# adc.net
KiCad netlist of a schematic drawn in EAGLE
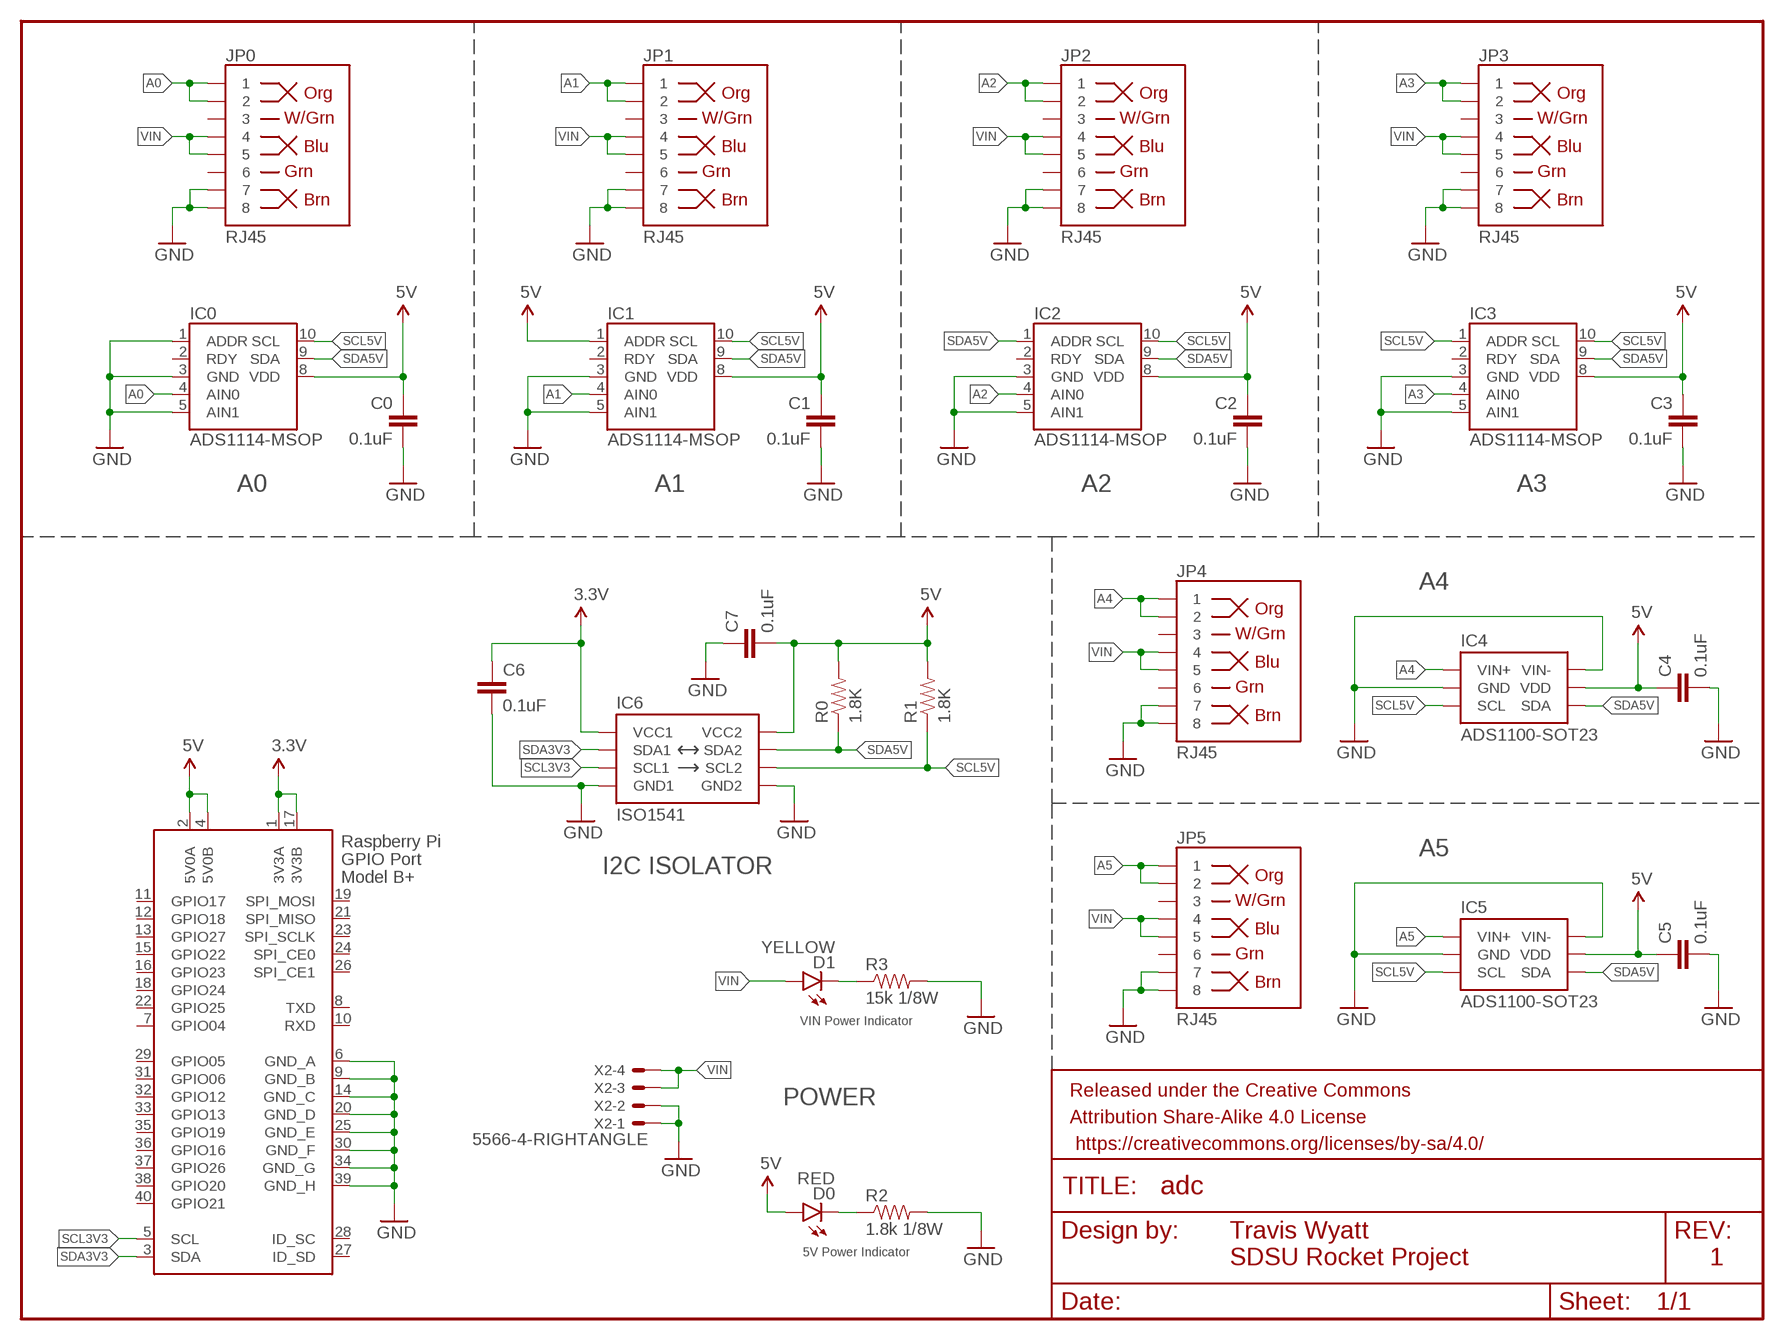
[diagram p0: schematic, sheet 1]

(export (version "E")
  (design (tool "Eeschema 10.0.6"))
  (components
    (comp (ref "C0")
      (value "0.1uF")
      (footprint "eagle-import:0603-CAP")
      (libsource (lib "eagle-import") (part "CAP0603-CAP"))
    )
    (comp (ref "C1")
      (value "0.1uF")
      (footprint "eagle-import:0603-CAP")
      (libsource (lib "eagle-import") (part "CAP0603-CAP"))
    )
    (comp (ref "C2")
      (value "0.1uF")
      (footprint "eagle-import:0603-CAP")
      (libsource (lib "eagle-import") (part "CAP0603-CAP"))
    )
    (comp (ref "C3")
      (value "0.1uF")
      (footprint "eagle-import:0603-CAP")
      (libsource (lib "eagle-import") (part "CAP0603-CAP"))
    )
    (comp (ref "C4")
      (value "0.1uF")
      (footprint "eagle-import:0603-CAP")
      (libsource (lib "eagle-import") (part "CAP0603-CAP"))
    )
    (comp (ref "C5")
      (value "0.1uF")
      (footprint "eagle-import:0603-CAP")
      (libsource (lib "eagle-import") (part "CAP0603-CAP"))
    )
    (comp (ref "C6")
      (value "0.1uF")
      (footprint "eagle-import:0603-CAP")
      (libsource (lib "eagle-import") (part "CAP0603-CAP"))
    )
    (comp (ref "C7")
      (value "0.1uF")
      (footprint "eagle-import:0603-CAP")
      (libsource (lib "eagle-import") (part "CAP0603-CAP"))
    )
    (comp (ref "D0")
      (value "RED")
      (footprint "eagle-import:LED-0603")
      (libsource (lib "eagle-import") (part "LED0603"))
    )
    (comp (ref "D1")
      (value "YELLOW")
      (footprint "eagle-import:LED-0603")
      (libsource (lib "eagle-import") (part "LED0603"))
    )
    (comp (ref "FRAME1")
      (value "FRAME-LETTER")
      (footprint "eagle-import:CREATIVE_COMMONS")
      (libsource (lib "eagle-import") (part "FRAME-LETTER"))
    )
    (comp (ref "IC0")
      (value "ADS1114-MSOP")
      (footprint "eagle-import:MSOP10")
      (libsource (lib "eagle-import") (part "ADS1114-MSOP"))
    )
    (comp (ref "IC1")
      (value "ADS1114-MSOP")
      (footprint "eagle-import:MSOP10")
      (libsource (lib "eagle-import") (part "ADS1114-MSOP"))
    )
    (comp (ref "IC2")
      (value "ADS1114-MSOP")
      (footprint "eagle-import:MSOP10")
      (libsource (lib "eagle-import") (part "ADS1114-MSOP"))
    )
    (comp (ref "IC3")
      (value "ADS1114-MSOP")
      (footprint "eagle-import:MSOP10")
      (libsource (lib "eagle-import") (part "ADS1114-MSOP"))
    )
    (comp (ref "IC4")
      (value "ADS1100-SOT23")
      (footprint "eagle-import:SOT23-6")
      (libsource (lib "eagle-import") (part "ADS1100-SOT23"))
    )
    (comp (ref "IC5")
      (value "ADS1100-SOT23")
      (footprint "eagle-import:SOT23-6")
      (libsource (lib "eagle-import") (part "ADS1100-SOT23"))
    )
    (comp (ref "IC6")
      (value "ISO1541")
      (footprint "eagle-import:SOIC8")
      (libsource (lib "eagle-import") (part "ISO1541-SOIC"))
    )
    (comp (ref "JP0")
      (value "RJ45")
      (footprint "eagle-import:RJ45-8")
      (libsource (lib "eagle-import") (part "RJ45-8PTH"))
    )
    (comp (ref "JP1")
      (value "RJ45")
      (footprint "eagle-import:RJ45-8")
      (libsource (lib "eagle-import") (part "RJ45-8PTH"))
    )
    (comp (ref "JP2")
      (value "RJ45")
      (footprint "eagle-import:RJ45-8")
      (libsource (lib "eagle-import") (part "RJ45-8PTH"))
    )
    (comp (ref "JP3")
      (value "RJ45")
      (footprint "eagle-import:RJ45-8")
      (libsource (lib "eagle-import") (part "RJ45-8PTH"))
    )
    (comp (ref "JP4")
      (value "RJ45")
      (footprint "eagle-import:RJ45-8")
      (libsource (lib "eagle-import") (part "RJ45-8PTH"))
    )
    (comp (ref "JP5")
      (value "RJ45")
      (footprint "eagle-import:RJ45-8")
      (libsource (lib "eagle-import") (part "RJ45-8PTH"))
    )
    (comp (ref "R0")
      (value "1.8K")
      (footprint "eagle-import:0603-RES")
      (libsource (lib "eagle-import") (part "RESISTOR0603-RES"))
    )
    (comp (ref "R1")
      (value "1.8K")
      (footprint "eagle-import:0603-RES")
      (libsource (lib "eagle-import") (part "RESISTOR0603-RES"))
    )
    (comp (ref "R2")
      (value "1.8k 1/8W")
      (footprint "eagle-import:0603-RES")
      (libsource (lib "eagle-import") (part "SparkFun-Resistors_RESISTOR0603-RES"))
    )
    (comp (ref "R3")
      (value "15k 1/8W")
      (footprint "eagle-import:0603-RES")
      (libsource (lib "eagle-import") (part "SparkFun-Resistors_RESISTOR0603-RES"))
    )
    (comp (ref "X1")
      (value "RASPI_BOARD_B+#_H")
      (footprint "eagle-import:RASPI_BOARD_B+HAT")
      (libsource (lib "eagle-import") (part "RASPI_BOARD_B+#_H"))
    )
    (comp (ref "X2")
      (value "5566-4-RIGHTANGLE")
      (footprint "eagle-import:5566-4")
      (libsource (lib "eagle-import") (part "5566-4-RIGHTANGLE"))
    )
  )
  (nets
    (net (code "1") (name "3.3V") (class "Default")
      (node (ref "C6") (pin "1") (pinfunction "1_1") (pintype "passive"))
      (node (ref "IC6") (pin "1") (pinfunction "VCC1_1") (pintype "power_in"))
      (node (ref "X1") (pin "1") (pinfunction "3V3A_1") (pintype "power_in"))
      (node (ref "X1") (pin "17") (pinfunction "3V3B_17") (pintype "power_in"))
    )
    (net (code "2") (name "5V") (class "Default")
      (node (ref "C0") (pin "1") (pinfunction "1_1") (pintype "passive"))
      (node (ref "C1") (pin "1") (pinfunction "1_1") (pintype "passive"))
      (node (ref "C2") (pin "1") (pinfunction "1_1") (pintype "passive"))
      (node (ref "C3") (pin "1") (pinfunction "1_1") (pintype "passive"))
      (node (ref "C4") (pin "1") (pinfunction "1_1") (pintype "passive"))
      (node (ref "C5") (pin "1") (pinfunction "1_1") (pintype "passive"))
      (node (ref "C7") (pin "2") (pinfunction "2_2") (pintype "passive"))
      (node (ref "D0") (pin "A") (pinfunction "A_A") (pintype "passive"))
      (node (ref "IC0") (pin "8") (pinfunction "VDD_8") (pintype "power_in"))
      (node (ref "IC1") (pin "1") (pinfunction "ADDR_1") (pintype "bidirectional"))
      (node (ref "IC1") (pin "8") (pinfunction "VDD_8") (pintype "power_in"))
      (node (ref "IC2") (pin "8") (pinfunction "VDD_8") (pintype "power_in"))
      (node (ref "IC3") (pin "8") (pinfunction "VDD_8") (pintype "power_in"))
      (node (ref "IC4") (pin "5") (pinfunction "VDD_5") (pintype "power_in"))
      (node (ref "IC5") (pin "5") (pinfunction "VDD_5") (pintype "power_in"))
      (node (ref "IC6") (pin "8") (pinfunction "VCC2_8") (pintype "power_in"))
      (node (ref "R0") (pin "2") (pinfunction "2_2") (pintype "passive"))
      (node (ref "R1") (pin "2") (pinfunction "2_2") (pintype "passive"))
      (node (ref "X1") (pin "2") (pinfunction "5V0A_2") (pintype "power_in"))
      (node (ref "X1") (pin "4") (pinfunction "5V0B_4") (pintype "power_in"))
    )
    (net (code "3") (name "A0") (class "Default")
      (node (ref "IC0") (pin "4") (pinfunction "AIN0_4") (pintype "input"))
      (node (ref "JP0") (pin "1") (pinfunction "1_1") (pintype "bidirectional"))
      (node (ref "JP0") (pin "2") (pinfunction "2_2") (pintype "bidirectional"))
    )
    (net (code "4") (name "A1") (class "Default")
      (node (ref "IC1") (pin "4") (pinfunction "AIN0_4") (pintype "input"))
      (node (ref "JP1") (pin "1") (pinfunction "1_1") (pintype "bidirectional"))
      (node (ref "JP1") (pin "2") (pinfunction "2_2") (pintype "bidirectional"))
    )
    (net (code "5") (name "A2") (class "Default")
      (node (ref "IC2") (pin "4") (pinfunction "AIN0_4") (pintype "input"))
      (node (ref "JP2") (pin "1") (pinfunction "1_1") (pintype "bidirectional"))
      (node (ref "JP2") (pin "2") (pinfunction "2_2") (pintype "bidirectional"))
    )
    (net (code "6") (name "A3") (class "Default")
      (node (ref "IC3") (pin "4") (pinfunction "AIN0_4") (pintype "input"))
      (node (ref "JP3") (pin "1") (pinfunction "1_1") (pintype "bidirectional"))
      (node (ref "JP3") (pin "2") (pinfunction "2_2") (pintype "bidirectional"))
    )
    (net (code "7") (name "A4") (class "Default")
      (node (ref "IC4") (pin "1") (pinfunction "VIN+_1") (pintype "input"))
      (node (ref "JP4") (pin "1") (pinfunction "1_1") (pintype "bidirectional"))
      (node (ref "JP4") (pin "2") (pinfunction "2_2") (pintype "bidirectional"))
    )
    (net (code "8") (name "A5") (class "Default")
      (node (ref "IC5") (pin "1") (pinfunction "VIN+_1") (pintype "input"))
      (node (ref "JP5") (pin "1") (pinfunction "1_1") (pintype "bidirectional"))
      (node (ref "JP5") (pin "2") (pinfunction "2_2") (pintype "bidirectional"))
    )
    (net (code "9") (name "GND") (class "Default")
      (node (ref "C0") (pin "2") (pinfunction "2_2") (pintype "passive"))
      (node (ref "C1") (pin "2") (pinfunction "2_2") (pintype "passive"))
      (node (ref "C2") (pin "2") (pinfunction "2_2") (pintype "passive"))
      (node (ref "C3") (pin "2") (pinfunction "2_2") (pintype "passive"))
      (node (ref "C4") (pin "2") (pinfunction "2_2") (pintype "passive"))
      (node (ref "C5") (pin "2") (pinfunction "2_2") (pintype "passive"))
      (node (ref "C6") (pin "2") (pinfunction "2_2") (pintype "passive"))
      (node (ref "C7") (pin "1") (pinfunction "1_1") (pintype "passive"))
      (node (ref "IC0") (pin "1") (pinfunction "ADDR_1") (pintype "bidirectional"))
      (node (ref "IC0") (pin "3") (pinfunction "GND_3") (pintype "power_in"))
      (node (ref "IC0") (pin "5") (pinfunction "AIN1_5") (pintype "input"))
      (node (ref "IC1") (pin "3") (pinfunction "GND_3") (pintype "power_in"))
      (node (ref "IC1") (pin "5") (pinfunction "AIN1_5") (pintype "input"))
      (node (ref "IC2") (pin "3") (pinfunction "GND_3") (pintype "power_in"))
      (node (ref "IC2") (pin "5") (pinfunction "AIN1_5") (pintype "input"))
      (node (ref "IC3") (pin "3") (pinfunction "GND_3") (pintype "power_in"))
      (node (ref "IC3") (pin "5") (pinfunction "AIN1_5") (pintype "input"))
      (node (ref "IC4") (pin "2") (pinfunction "GND_2") (pintype "power_in"))
      (node (ref "IC4") (pin "6") (pinfunction "VIN-_6") (pintype "input"))
      (node (ref "IC5") (pin "2") (pinfunction "GND_2") (pintype "power_in"))
      (node (ref "IC5") (pin "6") (pinfunction "VIN-_6") (pintype "input"))
      (node (ref "IC6") (pin "4") (pinfunction "GND1_4") (pintype "power_in"))
      (node (ref "IC6") (pin "5") (pinfunction "GND2_5") (pintype "power_in"))
      (node (ref "JP0") (pin "7") (pinfunction "7_7") (pintype "bidirectional"))
      (node (ref "JP0") (pin "8") (pinfunction "8_8") (pintype "bidirectional"))
      (node (ref "JP1") (pin "7") (pinfunction "7_7") (pintype "bidirectional"))
      (node (ref "JP1") (pin "8") (pinfunction "8_8") (pintype "bidirectional"))
      (node (ref "JP2") (pin "7") (pinfunction "7_7") (pintype "bidirectional"))
      (node (ref "JP2") (pin "8") (pinfunction "8_8") (pintype "bidirectional"))
      (node (ref "JP3") (pin "7") (pinfunction "7_7") (pintype "bidirectional"))
      (node (ref "JP3") (pin "8") (pinfunction "8_8") (pintype "bidirectional"))
      (node (ref "JP4") (pin "7") (pinfunction "7_7") (pintype "bidirectional"))
      (node (ref "JP4") (pin "8") (pinfunction "8_8") (pintype "bidirectional"))
      (node (ref "JP5") (pin "7") (pinfunction "7_7") (pintype "bidirectional"))
      (node (ref "JP5") (pin "8") (pinfunction "8_8") (pintype "bidirectional"))
      (node (ref "R2") (pin "2") (pinfunction "2_2") (pintype "passive"))
      (node (ref "R3") (pin "2") (pinfunction "2_2") (pintype "passive"))
      (node (ref "X1") (pin "14") (pinfunction "GND_C_14") (pintype "power_in"))
      (node (ref "X1") (pin "20") (pinfunction "GND_D_20") (pintype "power_in"))
      (node (ref "X1") (pin "25") (pinfunction "GND_E_25") (pintype "power_in"))
      (node (ref "X1") (pin "30") (pinfunction "GND_F_30") (pintype "power_in"))
      (node (ref "X1") (pin "34") (pinfunction "GND_G_34") (pintype "power_in"))
      (node (ref "X1") (pin "39") (pinfunction "GND_H_39") (pintype "power_in"))
      (node (ref "X1") (pin "6") (pinfunction "GND_A_6") (pintype "power_in"))
      (node (ref "X1") (pin "9") (pinfunction "GND_B_9") (pintype "power_in"))
      (node (ref "X2") (pin "1") (pinfunction "S_1") (pintype "passive"))
      (node (ref "X2") (pin "2") (pinfunction "S_2") (pintype "passive"))
    )
    (net (code "10") (name "Net-(D0-PadC)") (class "Default")
      (node (ref "D0") (pin "C") (pinfunction "C_C") (pintype "passive"))
      (node (ref "R2") (pin "1") (pinfunction "1_1") (pintype "passive"))
    )
    (net (code "11") (name "Net-(D1-PadC)") (class "Default")
      (node (ref "D1") (pin "C") (pinfunction "C_C") (pintype "passive"))
      (node (ref "R3") (pin "1") (pinfunction "1_1") (pintype "passive"))
    )
    (net (code "12") (name "SCL3V3") (class "Default")
      (node (ref "IC6") (pin "3") (pinfunction "SCL1_3") (pintype "input"))
      (node (ref "X1") (pin "5") (pinfunction "SCL_5") (pintype "bidirectional"))
    )
    (net (code "13") (name "SCL5V") (class "Default")
      (node (ref "IC0") (pin "10") (pinfunction "SCL_10") (pintype "bidirectional"))
      (node (ref "IC1") (pin "10") (pinfunction "SCL_10") (pintype "bidirectional"))
      (node (ref "IC2") (pin "10") (pinfunction "SCL_10") (pintype "bidirectional"))
      (node (ref "IC3") (pin "1") (pinfunction "ADDR_1") (pintype "bidirectional"))
      (node (ref "IC3") (pin "10") (pinfunction "SCL_10") (pintype "bidirectional"))
      (node (ref "IC4") (pin "3") (pinfunction "SCL_3") (pintype "input"))
      (node (ref "IC5") (pin "3") (pinfunction "SCL_3") (pintype "input"))
      (node (ref "IC6") (pin "6") (pinfunction "SCL2_6") (pintype "output"))
      (node (ref "R1") (pin "1") (pinfunction "1_1") (pintype "passive"))
    )
    (net (code "14") (name "SDA3V3") (class "Default")
      (node (ref "IC6") (pin "2") (pinfunction "SDA1_2") (pintype "bidirectional"))
      (node (ref "X1") (pin "3") (pinfunction "SDA_3") (pintype "bidirectional"))
    )
    (net (code "15") (name "SDA5V") (class "Default")
      (node (ref "IC0") (pin "9") (pinfunction "SDA_9") (pintype "bidirectional"))
      (node (ref "IC1") (pin "9") (pinfunction "SDA_9") (pintype "bidirectional"))
      (node (ref "IC2") (pin "1") (pinfunction "ADDR_1") (pintype "bidirectional"))
      (node (ref "IC2") (pin "9") (pinfunction "SDA_9") (pintype "bidirectional"))
      (node (ref "IC3") (pin "9") (pinfunction "SDA_9") (pintype "bidirectional"))
      (node (ref "IC4") (pin "4") (pinfunction "SDA_4") (pintype "bidirectional"))
      (node (ref "IC5") (pin "4") (pinfunction "SDA_4") (pintype "bidirectional"))
      (node (ref "IC6") (pin "7") (pinfunction "SDA2_7") (pintype "bidirectional"))
      (node (ref "R0") (pin "1") (pinfunction "1_1") (pintype "passive"))
    )
    (net (code "16") (name "VIN") (class "Default")
      (node (ref "D1") (pin "A") (pinfunction "A_A") (pintype "passive"))
      (node (ref "JP0") (pin "4") (pinfunction "4_4") (pintype "bidirectional"))
      (node (ref "JP0") (pin "5") (pinfunction "5_5") (pintype "bidirectional"))
      (node (ref "JP1") (pin "4") (pinfunction "4_4") (pintype "bidirectional"))
      (node (ref "JP1") (pin "5") (pinfunction "5_5") (pintype "bidirectional"))
      (node (ref "JP2") (pin "4") (pinfunction "4_4") (pintype "bidirectional"))
      (node (ref "JP2") (pin "5") (pinfunction "5_5") (pintype "bidirectional"))
      (node (ref "JP3") (pin "4") (pinfunction "4_4") (pintype "bidirectional"))
      (node (ref "JP3") (pin "5") (pinfunction "5_5") (pintype "bidirectional"))
      (node (ref "JP4") (pin "4") (pinfunction "4_4") (pintype "bidirectional"))
      (node (ref "JP4") (pin "5") (pinfunction "5_5") (pintype "bidirectional"))
      (node (ref "JP5") (pin "4") (pinfunction "4_4") (pintype "bidirectional"))
      (node (ref "JP5") (pin "5") (pinfunction "5_5") (pintype "bidirectional"))
      (node (ref "X2") (pin "3") (pinfunction "S_3") (pintype "passive"))
      (node (ref "X2") (pin "4") (pinfunction "S_4") (pintype "passive"))
    )
    (net (code "17") (name "unconnected-(IC0-RDY-Pad2)") (class "Default")
      (node (ref "IC0") (pin "2") (pinfunction "RDY_2") (pintype "bidirectional"))
    )
    (net (code "18") (name "unconnected-(IC1-RDY-Pad2)") (class "Default")
      (node (ref "IC1") (pin "2") (pinfunction "RDY_2") (pintype "bidirectional"))
    )
    (net (code "19") (name "unconnected-(IC2-RDY-Pad2)") (class "Default")
      (node (ref "IC2") (pin "2") (pinfunction "RDY_2") (pintype "bidirectional"))
    )
    (net (code "20") (name "unconnected-(IC3-RDY-Pad2)") (class "Default")
      (node (ref "IC3") (pin "2") (pinfunction "RDY_2") (pintype "bidirectional"))
    )
    (net (code "21") (name "unconnected-(JP0-Pad3)") (class "Default")
      (node (ref "JP0") (pin "3") (pinfunction "3_3") (pintype "bidirectional"))
    )
    (net (code "22") (name "unconnected-(JP0-Pad6)") (class "Default")
      (node (ref "JP0") (pin "6") (pinfunction "6_6") (pintype "bidirectional"))
    )
    (net (code "23") (name "unconnected-(JP1-Pad3)") (class "Default")
      (node (ref "JP1") (pin "3") (pinfunction "3_3") (pintype "bidirectional"))
    )
    (net (code "24") (name "unconnected-(JP1-Pad6)") (class "Default")
      (node (ref "JP1") (pin "6") (pinfunction "6_6") (pintype "bidirectional"))
    )
    (net (code "25") (name "unconnected-(JP2-Pad3)") (class "Default")
      (node (ref "JP2") (pin "3") (pinfunction "3_3") (pintype "bidirectional"))
    )
    (net (code "26") (name "unconnected-(JP2-Pad6)") (class "Default")
      (node (ref "JP2") (pin "6") (pinfunction "6_6") (pintype "bidirectional"))
    )
    (net (code "27") (name "unconnected-(JP3-Pad3)") (class "Default")
      (node (ref "JP3") (pin "3") (pinfunction "3_3") (pintype "bidirectional"))
    )
    (net (code "28") (name "unconnected-(JP3-Pad6)") (class "Default")
      (node (ref "JP3") (pin "6") (pinfunction "6_6") (pintype "bidirectional"))
    )
    (net (code "29") (name "unconnected-(JP4-Pad3)") (class "Default")
      (node (ref "JP4") (pin "3") (pinfunction "3_3") (pintype "bidirectional"))
    )
    (net (code "30") (name "unconnected-(JP4-Pad6)") (class "Default")
      (node (ref "JP4") (pin "6") (pinfunction "6_6") (pintype "bidirectional"))
    )
    (net (code "31") (name "unconnected-(JP5-Pad3)") (class "Default")
      (node (ref "JP5") (pin "3") (pinfunction "3_3") (pintype "bidirectional"))
    )
    (net (code "32") (name "unconnected-(JP5-Pad6)") (class "Default")
      (node (ref "JP5") (pin "6") (pinfunction "6_6") (pintype "bidirectional"))
    )
    (net (code "33") (name "unconnected-(X1-GPIO04-Pad7)") (class "Default")
      (node (ref "X1") (pin "7") (pinfunction "GPIO04_7") (pintype "bidirectional"))
    )
    (net (code "34") (name "unconnected-(X1-GPIO05-Pad29)") (class "Default")
      (node (ref "X1") (pin "29") (pinfunction "GPIO05_29") (pintype "no_connect"))
    )
    (net (code "35") (name "unconnected-(X1-GPIO06-Pad31)") (class "Default")
      (node (ref "X1") (pin "31") (pinfunction "GPIO06_31") (pintype "no_connect"))
    )
    (net (code "36") (name "unconnected-(X1-GPIO12-Pad32)") (class "Default")
      (node (ref "X1") (pin "32") (pinfunction "GPIO12_32") (pintype "no_connect"))
    )
    (net (code "37") (name "unconnected-(X1-GPIO13-Pad33)") (class "Default")
      (node (ref "X1") (pin "33") (pinfunction "GPIO13_33") (pintype "no_connect"))
    )
    (net (code "38") (name "unconnected-(X1-GPIO16-Pad36)") (class "Default")
      (node (ref "X1") (pin "36") (pinfunction "GPIO16_36") (pintype "no_connect"))
    )
    (net (code "39") (name "unconnected-(X1-GPIO17-Pad11)") (class "Default")
      (node (ref "X1") (pin "11") (pinfunction "GPIO17_11") (pintype "bidirectional"))
    )
    (net (code "40") (name "unconnected-(X1-GPIO18-Pad12)") (class "Default")
      (node (ref "X1") (pin "12") (pinfunction "GPIO18_12") (pintype "bidirectional"))
    )
    (net (code "41") (name "unconnected-(X1-GPIO19-Pad35)") (class "Default")
      (node (ref "X1") (pin "35") (pinfunction "GPIO19_35") (pintype "no_connect"))
    )
    (net (code "42") (name "unconnected-(X1-GPIO20-Pad38)") (class "Default")
      (node (ref "X1") (pin "38") (pinfunction "GPIO20_38") (pintype "no_connect"))
    )
    (net (code "43") (name "unconnected-(X1-GPIO21-Pad40)") (class "Default")
      (node (ref "X1") (pin "40") (pinfunction "GPIO21_40") (pintype "no_connect"))
    )
    (net (code "44") (name "unconnected-(X1-GPIO22-Pad15)") (class "Default")
      (node (ref "X1") (pin "15") (pinfunction "GPIO22_15") (pintype "bidirectional"))
    )
    (net (code "45") (name "unconnected-(X1-GPIO23-Pad16)") (class "Default")
      (node (ref "X1") (pin "16") (pinfunction "GPIO23_16") (pintype "bidirectional"))
    )
    (net (code "46") (name "unconnected-(X1-GPIO24-Pad18)") (class "Default")
      (node (ref "X1") (pin "18") (pinfunction "GPIO24_18") (pintype "bidirectional"))
    )
    (net (code "47") (name "unconnected-(X1-GPIO25-Pad22)") (class "Default")
      (node (ref "X1") (pin "22") (pinfunction "GPIO25_22") (pintype "bidirectional"))
    )
    (net (code "48") (name "unconnected-(X1-GPIO26-Pad37)") (class "Default")
      (node (ref "X1") (pin "37") (pinfunction "GPIO26_37") (pintype "no_connect"))
    )
    (net (code "49") (name "unconnected-(X1-GPIO27-Pad13)") (class "Default")
      (node (ref "X1") (pin "13") (pinfunction "GPIO27_13") (pintype "bidirectional"))
    )
    (net (code "50") (name "unconnected-(X1-ID_SC-Pad28)") (class "Default")
      (node (ref "X1") (pin "28") (pinfunction "ID_SC_28") (pintype "no_connect"))
    )
    (net (code "51") (name "unconnected-(X1-ID_SD-Pad27)") (class "Default")
      (node (ref "X1") (pin "27") (pinfunction "ID_SD_27") (pintype "no_connect"))
    )
    (net (code "52") (name "unconnected-(X1-RXD-Pad10)") (class "Default")
      (node (ref "X1") (pin "10") (pinfunction "RXD_10") (pintype "bidirectional"))
    )
    (net (code "53") (name "unconnected-(X1-SPI_CE0-Pad24)") (class "Default")
      (node (ref "X1") (pin "24") (pinfunction "SPI_CE0_24") (pintype "bidirectional"))
    )
    (net (code "54") (name "unconnected-(X1-SPI_CE1-Pad26)") (class "Default")
      (node (ref "X1") (pin "26") (pinfunction "SPI_CE1_26") (pintype "bidirectional"))
    )
    (net (code "55") (name "unconnected-(X1-SPI_MISO-Pad21)") (class "Default")
      (node (ref "X1") (pin "21") (pinfunction "SPI_MISO_21") (pintype "bidirectional"))
    )
    (net (code "56") (name "unconnected-(X1-SPI_MOSI-Pad19)") (class "Default")
      (node (ref "X1") (pin "19") (pinfunction "SPI_MOSI_19") (pintype "bidirectional"))
    )
    (net (code "57") (name "unconnected-(X1-SPI_SCLK-Pad23)") (class "Default")
      (node (ref "X1") (pin "23") (pinfunction "SPI_SCLK_23") (pintype "bidirectional"))
    )
    (net (code "58") (name "unconnected-(X1-TXD-Pad8)") (class "Default")
      (node (ref "X1") (pin "8") (pinfunction "TXD_8") (pintype "bidirectional"))
    )
  )
)
